# SCH.net
KiCad netlist of a schematic drawn in Altium Designer
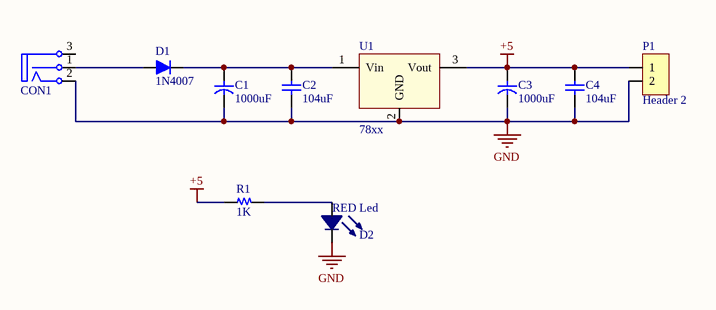
[diagram p0: SCH.SchDoc]

(export (version "E")
  (design (tool "Eeschema 10.0.6"))
  (components
    (comp (ref "C1")
      (value "1000uF")
      (footprint "CYL/D.400/LS.200")
      (description "Capacitor pol")
      (libsource (lib "chipfc_libs") (part "Capacitor"))
    )
    (comp (ref "C2")
      (value "104uF")
      (footprint "CAP Ceramic/W300")
      (description "Capacitor non-pol")
      (libsource (lib "chipfc_libs") (part "Capacitor NP"))
    )
    (comp (ref "C3")
      (value "1000uF")
      (footprint "CYL/D.400/LS.200")
      (description "Capacitor pol")
      (libsource (lib "chipfc_libs") (part "Capacitor"))
    )
    (comp (ref "C4")
      (value "104uF")
      (footprint "CAP Ceramic/W300")
      (description "Capacitor non-pol")
      (libsource (lib "chipfc_libs") (part "Capacitor NP"))
    )
    (comp (ref "CON1")
      (value "CON DC PWR")
      (footprint "CONN/DC/PWR/5.0MM")
      (description "DC input connector")
      (libsource (lib "connectors") (part "CON DC PWR"))
    )
    (comp (ref "D1")
      (value "1N4007")
      (footprint "DO-41")
      (description "Default Diode")
      (libsource (lib "chipfc_libs") (part "Diode"))
    )
    (comp (ref "D2")
      (value "RED Led")
      (footprint "LED_5mm_RED")
      (description "LED PTH 5mm Red.")
      (libsource (lib "LED") (part "LED_5mm_RED"))
    )
    (comp (ref "P1")
      (value "Header 2")
      (footprint "HDR/Terminal/2")
      (description "Header, 2-Pin")
      (libsource (lib "connectors") (part "Header 2"))
    )
    (comp (ref "R1")
      (value "1K")
      (footprint "R 1/4W/300")
      (description "Resistor")
      (libsource (lib "chipfc_libs") (part "Resistor"))
    )
    (comp (ref "U1")
      (value "78xx")
      (footprint "TO-220")
      (description "LDO Fixed Voltage regulator")
      (libsource (lib "chipfc_libs") (part "78xx"))
    )
  )
  (nets
    (net (code "1") (name "+5") (class "Default")
      (node (ref "C3") (pin "1") (pinfunction "1_1") (pintype "passive"))
      (node (ref "C4") (pin "1") (pinfunction "1_1") (pintype "passive"))
      (node (ref "P1") (pin "1") (pinfunction "1_1") (pintype "passive"))
      (node (ref "R1") (pin "1") (pinfunction "1_1") (pintype "passive"))
      (node (ref "U1") (pin "3") (pinfunction "Vout_3") (pintype "passive"))
    )
    (net (code "2") (name "GND") (class "Default")
      (node (ref "C1") (pin "2") (pinfunction "2_2") (pintype "passive"))
      (node (ref "C2") (pin "2") (pinfunction "2_2") (pintype "passive"))
      (node (ref "C3") (pin "2") (pinfunction "2_2") (pintype "passive"))
      (node (ref "C4") (pin "2") (pinfunction "2_2") (pintype "passive"))
      (node (ref "CON1") (pin "2") (pinfunction "T_2") (pintype "passive"))
      (node (ref "D2") (pin "2") (pinfunction "2_2") (pintype "passive"))
      (node (ref "P1") (pin "2") (pinfunction "2_2") (pintype "passive"))
      (node (ref "U1") (pin "2") (pinfunction "GND_2") (pintype "passive"))
    )
    (net (code "3") (name "Net-(CON1-S)") (class "Default")
      (node (ref "CON1") (pin "1") (pinfunction "S_1") (pintype "power_in"))
      (node (ref "D1") (pin "1") (pinfunction "A_1") (pintype "passive"))
    )
    (net (code "4") (name "Net-(D1-K)") (class "Default")
      (node (ref "C1") (pin "1") (pinfunction "1_1") (pintype "passive"))
      (node (ref "C2") (pin "1") (pinfunction "1_1") (pintype "passive"))
      (node (ref "D1") (pin "2") (pinfunction "K_2") (pintype "passive"))
      (node (ref "U1") (pin "1") (pinfunction "Vin_1") (pintype "power_in"))
    )
    (net (code "5") (name "Net-(D2-Pad1)") (class "Default")
      (node (ref "D2") (pin "1") (pinfunction "1_1") (pintype "passive"))
      (node (ref "R1") (pin "2") (pinfunction "2_2") (pintype "passive"))
    )
    (net (code "6") (name "unconnected-(CON1-TN-Pad3)") (class "Default")
      (node (ref "CON1") (pin "3") (pinfunction "TN_3") (pintype "passive"))
    )
  )
)
